# extBoard_sheet3_interrupt_generator.net
KiCad netlist of a schematic drawn in Altium Designer
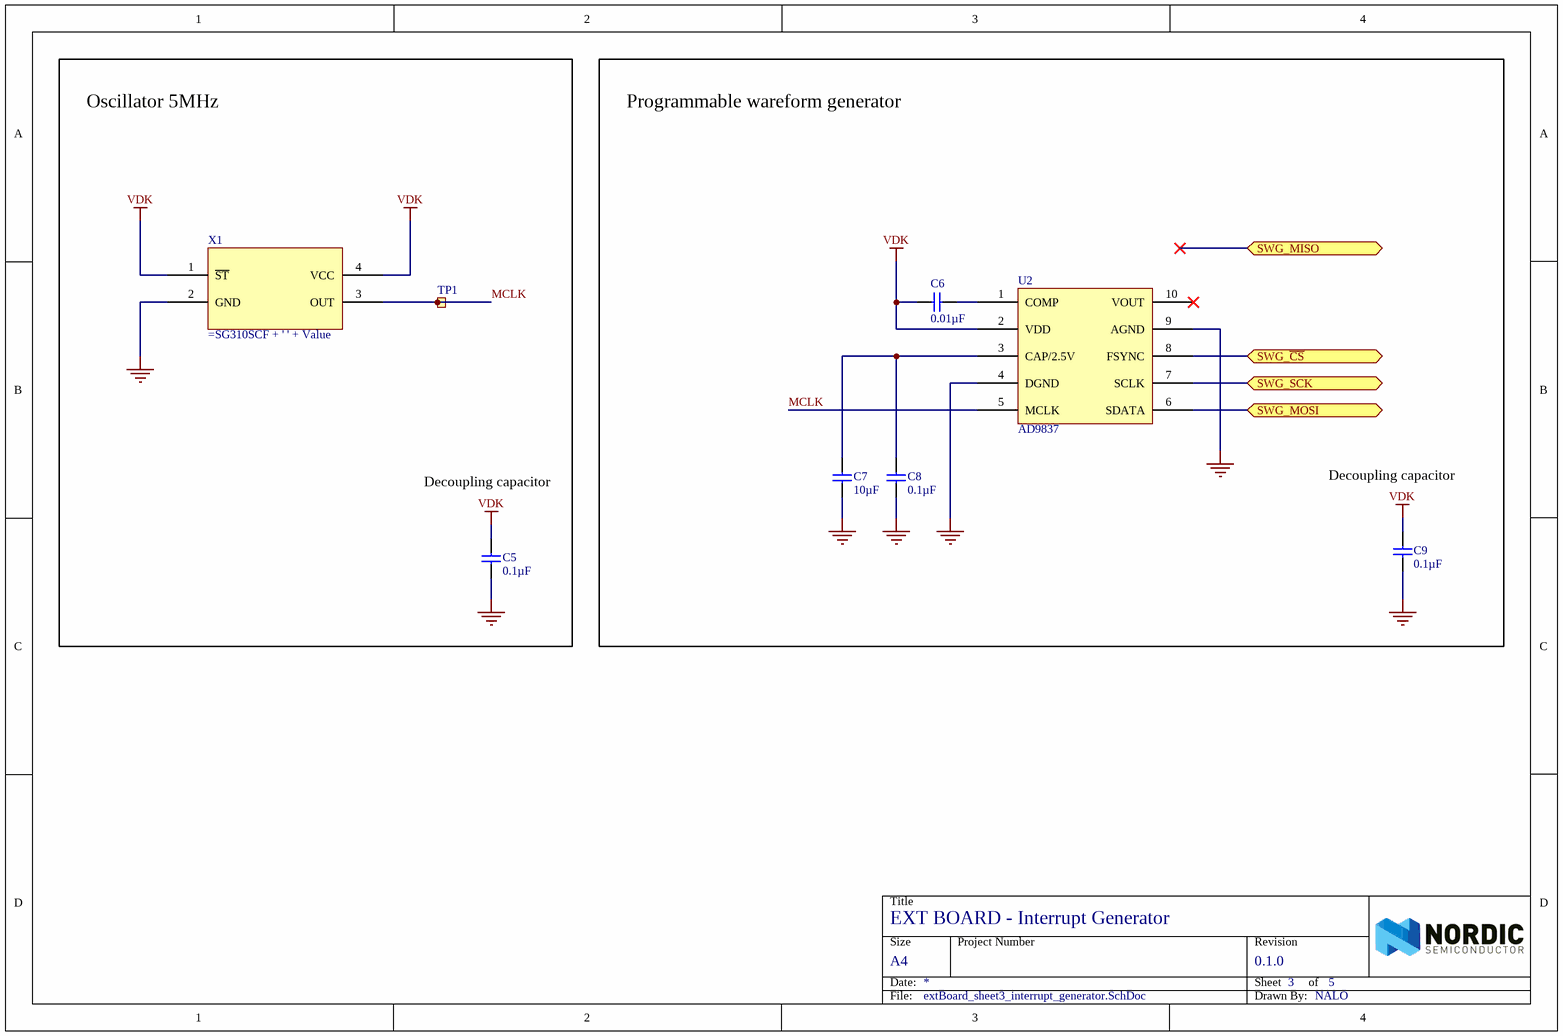
[diagram p0: extBoard_sheet3_interrupt_generator.SchDoc]

(export (version "E")
  (design (tool "Eeschema 10.0.6"))
  (components
    (comp (ref "C5")
      (value "0.1µF")
      (footprint "CAPC2012X11L")
      (description "Capacitor, X5R, ±10%")
      (fields (field (name "PART NUMBER") "C0805-4µ7") (field (name "PUBLISHER") "Nordic Semiconductor"))
      (libsource (lib "pca10056") (part "CAP_0805"))
    )
    (comp (ref "C6")
      (value "0.01µF")
      (footprint "CAPC2012X11L")
      (description "Capacitor, X5R, ±10%")
      (fields (field (name "PART NUMBER") "C0805-4µ7") (field (name "PUBLISHER") "Nordic Semiconductor"))
      (libsource (lib "pca10056") (part "CAP_0805"))
    )
    (comp (ref "C7")
      (value "10µF")
      (footprint "CAPC2012X11L")
      (description "Capacitor, X5R, ±10%")
      (fields (field (name "PART NUMBER") "C0805-4µ7") (field (name "PUBLISHER") "Nordic Semiconductor"))
      (libsource (lib "pca10056") (part "CAP_0805"))
    )
    (comp (ref "C8")
      (value "0.1µF")
      (footprint "CAPC2012X11L")
      (description "Capacitor, X5R, ±10%")
      (fields (field (name "PART NUMBER") "C0805-4µ7") (field (name "PUBLISHER") "Nordic Semiconductor"))
      (libsource (lib "pca10056") (part "CAP_0805"))
    )
    (comp (ref "C9")
      (value "0.1µF")
      (footprint "CAPC2012X11L")
      (description "Capacitor, X5R, ±10%")
      (fields (field (name "PART NUMBER") "C0805-4µ7") (field (name "PUBLISHER") "Nordic Semiconductor"))
      (libsource (lib "pca10056") (part "CAP_0805"))
    )
    (comp (ref "TP1")
      (value "TP")
      (footprint "TESTPAD-TH")
      (description "Testpoint, through hole")
      (fields (field (name "PART NUMBER") "Testpoint TH") (field (name "PUBLISHER") "Nordic Semiconductor"))
      (libsource (lib "pca10056") (part "Testpoint TH"))
    )
    (comp (ref "U2")
      (value "AD9837")
      (footprint "DFN50P300X300X95-10N")
      (libsource (lib "extBoard") (part "AD9837"))
    )
    (comp (ref "X1") (value "16MHz") (footprint "SG310SCF") (libsource (lib "extBoardLib") (part "SG310SCF")))
  )
  (nets
    (net (code "1") (name "/MCLK") (class "Default")
      (node (ref "TP1") (pin "1") (pinfunction "1_1") (pintype "passive"))
      (node (ref "U2") (pin "5") (pinfunction "MCLK_5") (pintype "passive"))
      (node (ref "X1") (pin "3") (pinfunction "OUT_3") (pintype "passive"))
    )
    (net (code "3") (name "/SWG_MOSI") (class "Default")
      (node (ref "U2") (pin "6") (pinfunction "SDATA_6") (pintype "passive"))
    )
    (net (code "4") (name "/SWG_SCK") (class "Default")
      (node (ref "U2") (pin "7") (pinfunction "SCLK_7") (pintype "passive"))
    )
    (net (code "5") (name "/SWG_~{CS}") (class "Default")
      (node (ref "U2") (pin "8") (pinfunction "FSYNC_8") (pintype "passive"))
    )
    (net (code "6") (name "GND") (class "Default")
      (node (ref "C5") (pin "1") (pinfunction "1_1") (pintype "passive"))
      (node (ref "C7") (pin "1") (pinfunction "1_1") (pintype "passive"))
      (node (ref "C8") (pin "1") (pinfunction "1_1") (pintype "passive"))
      (node (ref "C9") (pin "1") (pinfunction "1_1") (pintype "passive"))
      (node (ref "U2") (pin "4") (pinfunction "DGND_4") (pintype "passive"))
      (node (ref "U2") (pin "9") (pinfunction "AGND_9") (pintype "passive"))
      (node (ref "X1") (pin "2") (pinfunction "GND_2") (pintype "passive"))
    )
    (net (code "7") (name "Net-(U2-CAP{slash}2.5V)") (class "Default")
      (node (ref "C7") (pin "2") (pinfunction "2_2") (pintype "passive"))
      (node (ref "C8") (pin "2") (pinfunction "2_2") (pintype "passive"))
      (node (ref "U2") (pin "3") (pinfunction "CAP/2.5V_3") (pintype "passive"))
    )
    (net (code "8") (name "Net-(U2-COMP)") (class "Default")
      (node (ref "C6") (pin "1") (pinfunction "1_1") (pintype "passive"))
      (node (ref "U2") (pin "1") (pinfunction "COMP_1") (pintype "passive"))
    )
    (net (code "9") (name "VDK") (class "Default")
      (node (ref "C5") (pin "2") (pinfunction "2_2") (pintype "passive"))
      (node (ref "C6") (pin "2") (pinfunction "2_2") (pintype "passive"))
      (node (ref "C9") (pin "2") (pinfunction "2_2") (pintype "passive"))
      (node (ref "U2") (pin "2") (pinfunction "VDD_2") (pintype "passive"))
      (node (ref "X1") (pin "1") (pinfunction "~{ST}_1") (pintype "passive"))
      (node (ref "X1") (pin "4") (pinfunction "VCC_4") (pintype "passive"))
    )
    (net (code "10") (name "unconnected-(U2-VOUT-Pad10)") (class "Default")
      (node (ref "U2") (pin "10") (pinfunction "VOUT_10") (pintype "passive+no_connect"))
    )
  )
)
